# 10-DashLEDs.net
KiCad netlist of a schematic drawn in Altium Designer
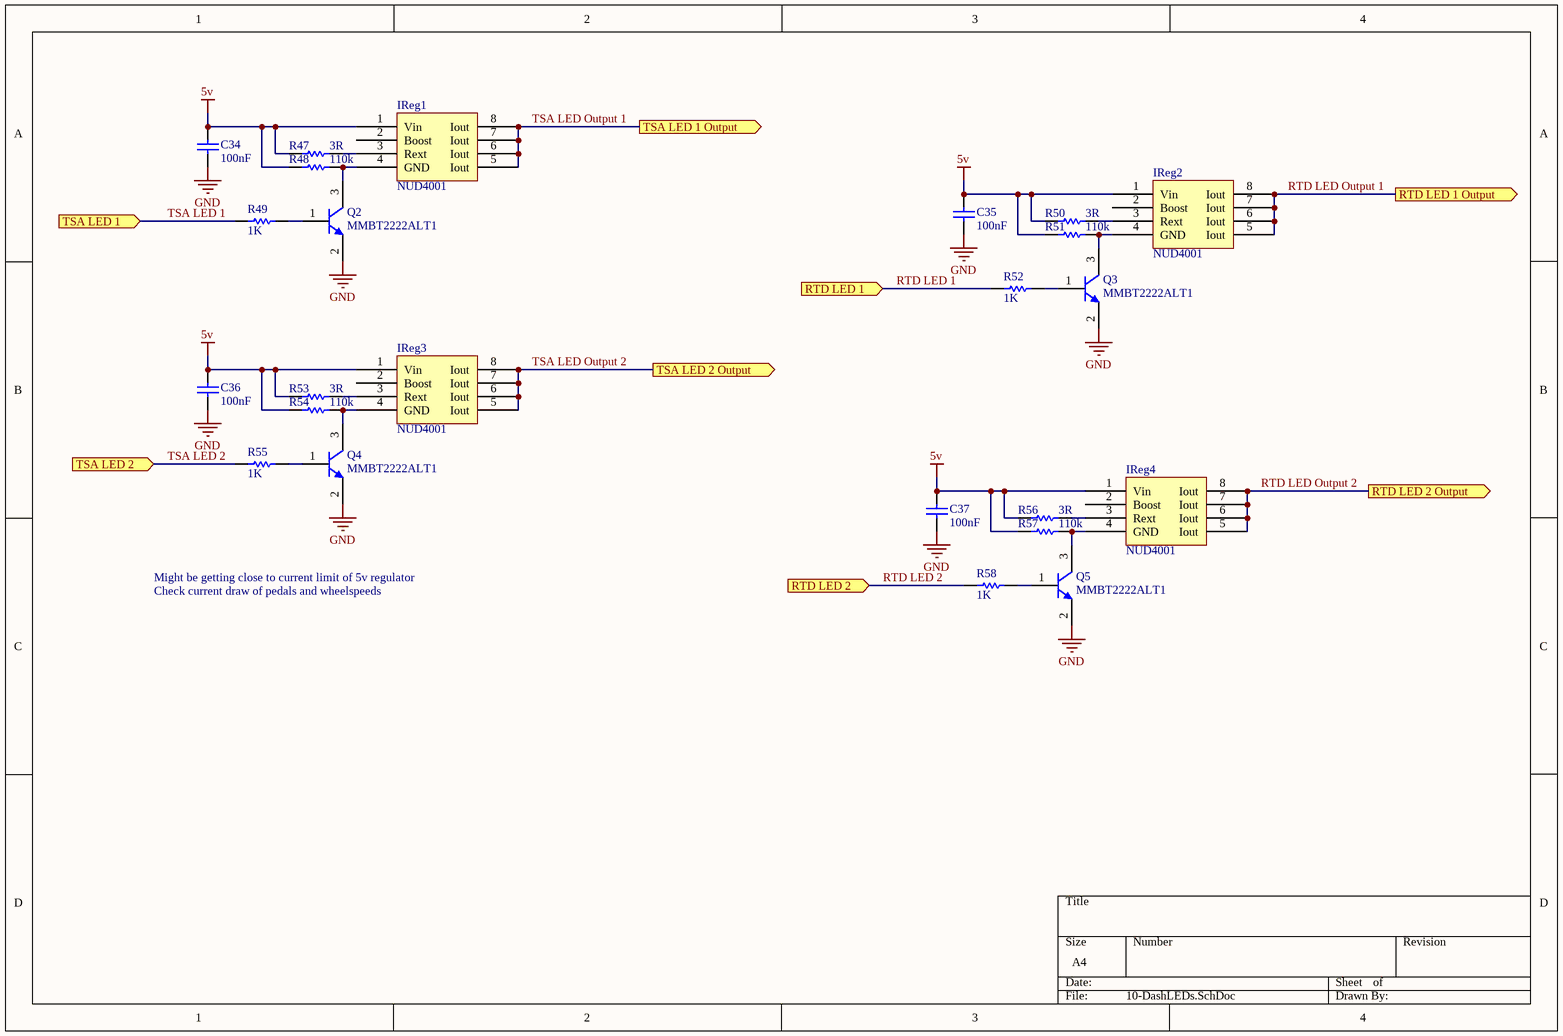
[diagram p0: 10-DashLEDs.SchDoc]

(export (version "E")
  (design (tool "Eeschema 10.0.6"))
  (components
    (comp (ref "C34")
      (value "100nF")
      (footprint "1608[0603]")
      (description "Capacitor")
      (fields
        (field (name "MANUFACTURER") "Yageo")
        (field (name "MANUFACTURER PART NUMBER") "CC0603KRX7R9BB104")
      )
      (libsource (lib "Miscellaneous Devices") (part "Cap"))
    )
    (comp (ref "C35")
      (value "100nF")
      (footprint "1608[0603]")
      (description "Capacitor")
      (fields
        (field (name "MANUFACTURER") "Yageo")
        (field (name "MANUFACTURER PART NUMBER") "CC0603KRX7R9BB104")
      )
      (libsource (lib "Miscellaneous Devices") (part "Cap"))
    )
    (comp (ref "C36")
      (value "100nF")
      (footprint "1608[0603]")
      (description "Capacitor")
      (fields
        (field (name "MANUFACTURER") "Yageo")
        (field (name "MANUFACTURER PART NUMBER") "CC0603KRX7R9BB104")
      )
      (libsource (lib "Miscellaneous Devices") (part "Cap"))
    )
    (comp (ref "C37")
      (value "100nF")
      (footprint "1608[0603]")
      (description "Capacitor")
      (fields
        (field (name "MANUFACTURER") "Yageo")
        (field (name "MANUFACTURER PART NUMBER") "CC0603KRX7R9BB104")
      )
      (libsource (lib "Miscellaneous Devices") (part "Cap"))
    )
    (comp (ref "IReg1")
      (value "NUD4001")
      (footprint "SO8_M")
      (fields
        (field (name "MANUFACTURER") "ON Semiconductor")
        (field (name "MANUFACTURER PART NUMBER") "NUD4001DR2G")
      )
      (libsource (lib "VCU Library") (part "LED Currnet Driver, 500mA, 30V max"))
    )
    (comp (ref "IReg2")
      (value "NUD4001")
      (footprint "SO8_M")
      (fields
        (field (name "MANUFACTURER") "ON Semiconductor")
        (field (name "MANUFACTURER PART NUMBER") "NUD4001DR2G")
      )
      (libsource (lib "VCU Library") (part "LED Currnet Driver, 500mA, 30V max"))
    )
    (comp (ref "IReg3")
      (value "NUD4001")
      (footprint "SO8_M")
      (fields
        (field (name "MANUFACTURER") "ON Semiconductor")
        (field (name "MANUFACTURER PART NUMBER") "NUD4001DR2G")
      )
      (libsource (lib "VCU Library") (part "LED Currnet Driver, 500mA, 30V max"))
    )
    (comp (ref "IReg4")
      (value "NUD4001")
      (footprint "SO8_M")
      (fields
        (field (name "MANUFACTURER") "ON Semiconductor")
        (field (name "MANUFACTURER PART NUMBER") "NUD4001DR2G")
      )
      (libsource (lib "VCU Library") (part "LED Currnet Driver, 500mA, 30V max"))
    )
    (comp (ref "Q2")
      (value "MMBT2222ALT1")
      (footprint "ONSC-SOT-23-3-318-08_V")
      (description "General Purpose Transistor, NPN Silicon, 3-Pin SOT-23, Tape and Reel")
      (fields (field (name "MANUFACTURER") "On Semiconductor"))
      (libsource (lib "Altium Content Vault") (part "ONSC-NPN-B1E2C3-3"))
    )
    (comp (ref "Q3")
      (value "MMBT2222ALT1")
      (footprint "ONSC-SOT-23-3-318-08_V")
      (description "General Purpose Transistor, NPN Silicon, 3-Pin SOT-23, Tape and Reel")
      (fields (field (name "MANUFACTURER") "On Semiconductor"))
      (libsource (lib "Altium Content Vault") (part "ONSC-NPN-B1E2C3-3"))
    )
    (comp (ref "Q4")
      (value "MMBT2222ALT1")
      (footprint "ONSC-SOT-23-3-318-08_V")
      (description "General Purpose Transistor, NPN Silicon, 3-Pin SOT-23, Tape and Reel")
      (fields (field (name "MANUFACTURER") "On Semiconductor"))
      (libsource (lib "Altium Content Vault") (part "ONSC-NPN-B1E2C3-3"))
    )
    (comp (ref "Q5")
      (value "MMBT2222ALT1")
      (footprint "ONSC-SOT-23-3-318-08_V")
      (description "General Purpose Transistor, NPN Silicon, 3-Pin SOT-23, Tape and Reel")
      (fields (field (name "MANUFACTURER") "On Semiconductor"))
      (libsource (lib "Altium Content Vault") (part "ONSC-NPN-B1E2C3-3"))
    )
    (comp (ref "R47")
      (value "3R")
      (footprint "1608[0603]")
      (description "Resistor")
      (fields
        (field (name "MANUFACTURER") "Yageo")
        (field (name "MANUFACTURER PART NUMBER") "RC0603FR-072RL")
      )
      (libsource (lib "Miscellaneous Devices") (part "Res1"))
    )
    (comp (ref "R48")
      (value "110k")
      (footprint "1608[0603]")
      (description "Resistor")
      (fields
        (field (name "MANUFACTURER") "Yageo")
        (field (name "MANUFACTURER PART NUMBER") "RC0603JR-07110KL")
      )
      (libsource (lib "Miscellaneous Devices") (part "Res1"))
    )
    (comp (ref "R49")
      (value "1K")
      (footprint "1608[0603]")
      (description "Resistor")
      (fields
        (field (name "MANUFACTURER") "Panasonic Electronic Components")
        (field (name "MANUFACTURER PART NUMBER") "ERJ-PA3F1001V")
      )
      (libsource (lib "Miscellaneous Devices") (part "Res1"))
    )
    (comp (ref "R50")
      (value "3R")
      (footprint "1608[0603]")
      (description "Resistor")
      (fields
        (field (name "MANUFACTURER") "Yageo")
        (field (name "MANUFACTURER PART NUMBER") "RC0603FR-072RL")
      )
      (libsource (lib "Miscellaneous Devices") (part "Res1"))
    )
    (comp (ref "R51")
      (value "110k")
      (footprint "1608[0603]")
      (description "Resistor")
      (fields
        (field (name "MANUFACTURER") "Yageo")
        (field (name "MANUFACTURER PART NUMBER") "RC0603JR-07110KL")
      )
      (libsource (lib "Miscellaneous Devices") (part "Res1"))
    )
    (comp (ref "R52")
      (value "1K")
      (footprint "1608[0603]")
      (description "Resistor")
      (fields
        (field (name "MANUFACTURER") "Panasonic Electronic Components")
        (field (name "MANUFACTURER PART NUMBER") "ERJ-PA3F1001V")
      )
      (libsource (lib "Miscellaneous Devices") (part "Res1"))
    )
    (comp (ref "R53")
      (value "3R")
      (footprint "1608[0603]")
      (description "Resistor")
      (fields
        (field (name "MANUFACTURER") "Yageo")
        (field (name "MANUFACTURER PART NUMBER") "RC0603FR-072RL")
      )
      (libsource (lib "Miscellaneous Devices") (part "Res1"))
    )
    (comp (ref "R54")
      (value "110k")
      (footprint "1608[0603]")
      (description "Resistor")
      (fields
        (field (name "MANUFACTURER") "Yageo")
        (field (name "MANUFACTURER PART NUMBER") "RC0603JR-07110KL")
      )
      (libsource (lib "Miscellaneous Devices") (part "Res1"))
    )
    (comp (ref "R55")
      (value "1K")
      (footprint "1608[0603]")
      (description "Resistor")
      (fields
        (field (name "MANUFACTURER") "Panasonic Electronic Components")
        (field (name "MANUFACTURER PART NUMBER") "ERJ-PA3F1001V")
      )
      (libsource (lib "Miscellaneous Devices") (part "Res1"))
    )
    (comp (ref "R56")
      (value "3R")
      (footprint "1608[0603]")
      (description "Resistor")
      (fields
        (field (name "MANUFACTURER") "Yageo")
        (field (name "MANUFACTURER PART NUMBER") "RC0603FR-072RL")
      )
      (libsource (lib "Miscellaneous Devices") (part "Res1"))
    )
    (comp (ref "R57")
      (value "110k")
      (footprint "1608[0603]")
      (description "Resistor")
      (fields
        (field (name "MANUFACTURER") "Yageo")
        (field (name "MANUFACTURER PART NUMBER") "RC0603JR-07110KL")
      )
      (libsource (lib "Miscellaneous Devices") (part "Res1"))
    )
    (comp (ref "R58")
      (value "1K")
      (footprint "1608[0603]")
      (description "Resistor")
      (fields
        (field (name "MANUFACTURER") "Panasonic Electronic Components")
        (field (name "MANUFACTURER PART NUMBER") "ERJ-PA3F1001V")
      )
      (libsource (lib "Miscellaneous Devices") (part "Res1"))
    )
  )
  (nets
    (net (code "1") (name "/RTD LED 1") (class "Default")
      (node (ref "R52") (pin "2") (pinfunction "2_2") (pintype "passive"))
    )
    (net (code "2") (name "/RTD LED 2") (class "Default")
      (node (ref "R58") (pin "2") (pinfunction "2_2") (pintype "passive"))
    )
    (net (code "3") (name "/RTD LED Output 1") (class "Default")
      (node (ref "IReg2") (pin "5") (pinfunction "Iout_5") (pintype "passive"))
      (node (ref "IReg2") (pin "6") (pinfunction "Iout_6") (pintype "passive"))
      (node (ref "IReg2") (pin "7") (pinfunction "Iout_7") (pintype "passive"))
      (node (ref "IReg2") (pin "8") (pinfunction "Iout_8") (pintype "passive"))
    )
    (net (code "4") (name "/RTD LED Output 2") (class "Default")
      (node (ref "IReg4") (pin "5") (pinfunction "Iout_5") (pintype "passive"))
      (node (ref "IReg4") (pin "6") (pinfunction "Iout_6") (pintype "passive"))
      (node (ref "IReg4") (pin "7") (pinfunction "Iout_7") (pintype "passive"))
      (node (ref "IReg4") (pin "8") (pinfunction "Iout_8") (pintype "passive"))
    )
    (net (code "5") (name "/TSA LED 1") (class "Default")
      (node (ref "R49") (pin "2") (pinfunction "2_2") (pintype "passive"))
    )
    (net (code "6") (name "/TSA LED 2") (class "Default")
      (node (ref "R55") (pin "2") (pinfunction "2_2") (pintype "passive"))
    )
    (net (code "7") (name "/TSA LED Output 1") (class "Default")
      (node (ref "IReg1") (pin "5") (pinfunction "Iout_5") (pintype "passive"))
      (node (ref "IReg1") (pin "6") (pinfunction "Iout_6") (pintype "passive"))
      (node (ref "IReg1") (pin "7") (pinfunction "Iout_7") (pintype "passive"))
      (node (ref "IReg1") (pin "8") (pinfunction "Iout_8") (pintype "passive"))
    )
    (net (code "8") (name "/TSA LED Output 2") (class "Default")
      (node (ref "IReg3") (pin "5") (pinfunction "Iout_5") (pintype "passive"))
      (node (ref "IReg3") (pin "6") (pinfunction "Iout_6") (pintype "passive"))
      (node (ref "IReg3") (pin "7") (pinfunction "Iout_7") (pintype "passive"))
      (node (ref "IReg3") (pin "8") (pinfunction "Iout_8") (pintype "passive"))
    )
    (net (code "9") (name "5v") (class "Default")
      (node (ref "C34") (pin "2") (pinfunction "2_2") (pintype "passive"))
      (node (ref "C35") (pin "2") (pinfunction "2_2") (pintype "passive"))
      (node (ref "C36") (pin "2") (pinfunction "2_2") (pintype "passive"))
      (node (ref "C37") (pin "2") (pinfunction "2_2") (pintype "passive"))
      (node (ref "IReg1") (pin "1") (pinfunction "Vin_1") (pintype "passive"))
      (node (ref "IReg2") (pin "1") (pinfunction "Vin_1") (pintype "passive"))
      (node (ref "IReg3") (pin "1") (pinfunction "Vin_1") (pintype "passive"))
      (node (ref "IReg4") (pin "1") (pinfunction "Vin_1") (pintype "passive"))
      (node (ref "R47") (pin "1") (pinfunction "1_1") (pintype "passive"))
      (node (ref "R48") (pin "1") (pinfunction "1_1") (pintype "passive"))
      (node (ref "R50") (pin "1") (pinfunction "1_1") (pintype "passive"))
      (node (ref "R51") (pin "1") (pinfunction "1_1") (pintype "passive"))
      (node (ref "R53") (pin "1") (pinfunction "1_1") (pintype "passive"))
      (node (ref "R54") (pin "1") (pinfunction "1_1") (pintype "passive"))
      (node (ref "R56") (pin "1") (pinfunction "1_1") (pintype "passive"))
      (node (ref "R57") (pin "1") (pinfunction "1_1") (pintype "passive"))
    )
    (net (code "10") (name "GND") (class "Default")
      (node (ref "C34") (pin "1") (pinfunction "1_1") (pintype "passive"))
      (node (ref "C35") (pin "1") (pinfunction "1_1") (pintype "passive"))
      (node (ref "C36") (pin "1") (pinfunction "1_1") (pintype "passive"))
      (node (ref "C37") (pin "1") (pinfunction "1_1") (pintype "passive"))
      (node (ref "Q2") (pin "2") (pinfunction "E_2") (pintype "passive"))
      (node (ref "Q3") (pin "2") (pinfunction "E_2") (pintype "passive"))
      (node (ref "Q4") (pin "2") (pinfunction "E_2") (pintype "passive"))
      (node (ref "Q5") (pin "2") (pinfunction "E_2") (pintype "passive"))
    )
    (net (code "11") (name "Net-(IReg1-GND)") (class "Default")
      (node (ref "IReg1") (pin "4") (pinfunction "GND_4") (pintype "passive"))
      (node (ref "Q2") (pin "3") (pinfunction "C_3") (pintype "passive"))
      (node (ref "R48") (pin "2") (pinfunction "2_2") (pintype "passive"))
    )
    (net (code "12") (name "Net-(IReg1-Rext)") (class "Default")
      (node (ref "IReg1") (pin "3") (pinfunction "Rext_3") (pintype "passive"))
      (node (ref "R47") (pin "2") (pinfunction "2_2") (pintype "passive"))
    )
    (net (code "13") (name "Net-(IReg2-GND)") (class "Default")
      (node (ref "IReg2") (pin "4") (pinfunction "GND_4") (pintype "passive"))
      (node (ref "Q3") (pin "3") (pinfunction "C_3") (pintype "passive"))
      (node (ref "R51") (pin "2") (pinfunction "2_2") (pintype "passive"))
    )
    (net (code "14") (name "Net-(IReg2-Rext)") (class "Default")
      (node (ref "IReg2") (pin "3") (pinfunction "Rext_3") (pintype "passive"))
      (node (ref "R50") (pin "2") (pinfunction "2_2") (pintype "passive"))
    )
    (net (code "15") (name "Net-(IReg3-GND)") (class "Default")
      (node (ref "IReg3") (pin "4") (pinfunction "GND_4") (pintype "passive"))
      (node (ref "Q4") (pin "3") (pinfunction "C_3") (pintype "passive"))
      (node (ref "R54") (pin "2") (pinfunction "2_2") (pintype "passive"))
    )
    (net (code "16") (name "Net-(IReg3-Rext)") (class "Default")
      (node (ref "IReg3") (pin "3") (pinfunction "Rext_3") (pintype "passive"))
      (node (ref "R53") (pin "2") (pinfunction "2_2") (pintype "passive"))
    )
    (net (code "17") (name "Net-(IReg4-GND)") (class "Default")
      (node (ref "IReg4") (pin "4") (pinfunction "GND_4") (pintype "passive"))
      (node (ref "Q5") (pin "3") (pinfunction "C_3") (pintype "passive"))
      (node (ref "R57") (pin "2") (pinfunction "2_2") (pintype "passive"))
    )
    (net (code "18") (name "Net-(IReg4-Rext)") (class "Default")
      (node (ref "IReg4") (pin "3") (pinfunction "Rext_3") (pintype "passive"))
      (node (ref "R56") (pin "2") (pinfunction "2_2") (pintype "passive"))
    )
    (net (code "19") (name "Net-(Q2-B)") (class "Default")
      (node (ref "Q2") (pin "1") (pinfunction "B_1") (pintype "passive"))
      (node (ref "R49") (pin "1") (pinfunction "1_1") (pintype "passive"))
    )
    (net (code "20") (name "Net-(Q3-B)") (class "Default")
      (node (ref "Q3") (pin "1") (pinfunction "B_1") (pintype "passive"))
      (node (ref "R52") (pin "1") (pinfunction "1_1") (pintype "passive"))
    )
    (net (code "21") (name "Net-(Q4-B)") (class "Default")
      (node (ref "Q4") (pin "1") (pinfunction "B_1") (pintype "passive"))
      (node (ref "R55") (pin "1") (pinfunction "1_1") (pintype "passive"))
    )
    (net (code "22") (name "Net-(Q5-B)") (class "Default")
      (node (ref "Q5") (pin "1") (pinfunction "B_1") (pintype "passive"))
      (node (ref "R58") (pin "1") (pinfunction "1_1") (pintype "passive"))
    )
    (net (code "23") (name "unconnected-(IReg1-Boost-Pad2)") (class "Default")
      (node (ref "IReg1") (pin "2") (pinfunction "Boost_2") (pintype "passive"))
    )
    (net (code "24") (name "unconnected-(IReg2-Boost-Pad2)") (class "Default")
      (node (ref "IReg2") (pin "2") (pinfunction "Boost_2") (pintype "passive"))
    )
    (net (code "25") (name "unconnected-(IReg3-Boost-Pad2)") (class "Default")
      (node (ref "IReg3") (pin "2") (pinfunction "Boost_2") (pintype "passive"))
    )
    (net (code "26") (name "unconnected-(IReg4-Boost-Pad2)") (class "Default")
      (node (ref "IReg4") (pin "2") (pinfunction "Boost_2") (pintype "passive"))
    )
  )
)
